# TOP.net
KiCad netlist of a schematic drawn in Altium Designer
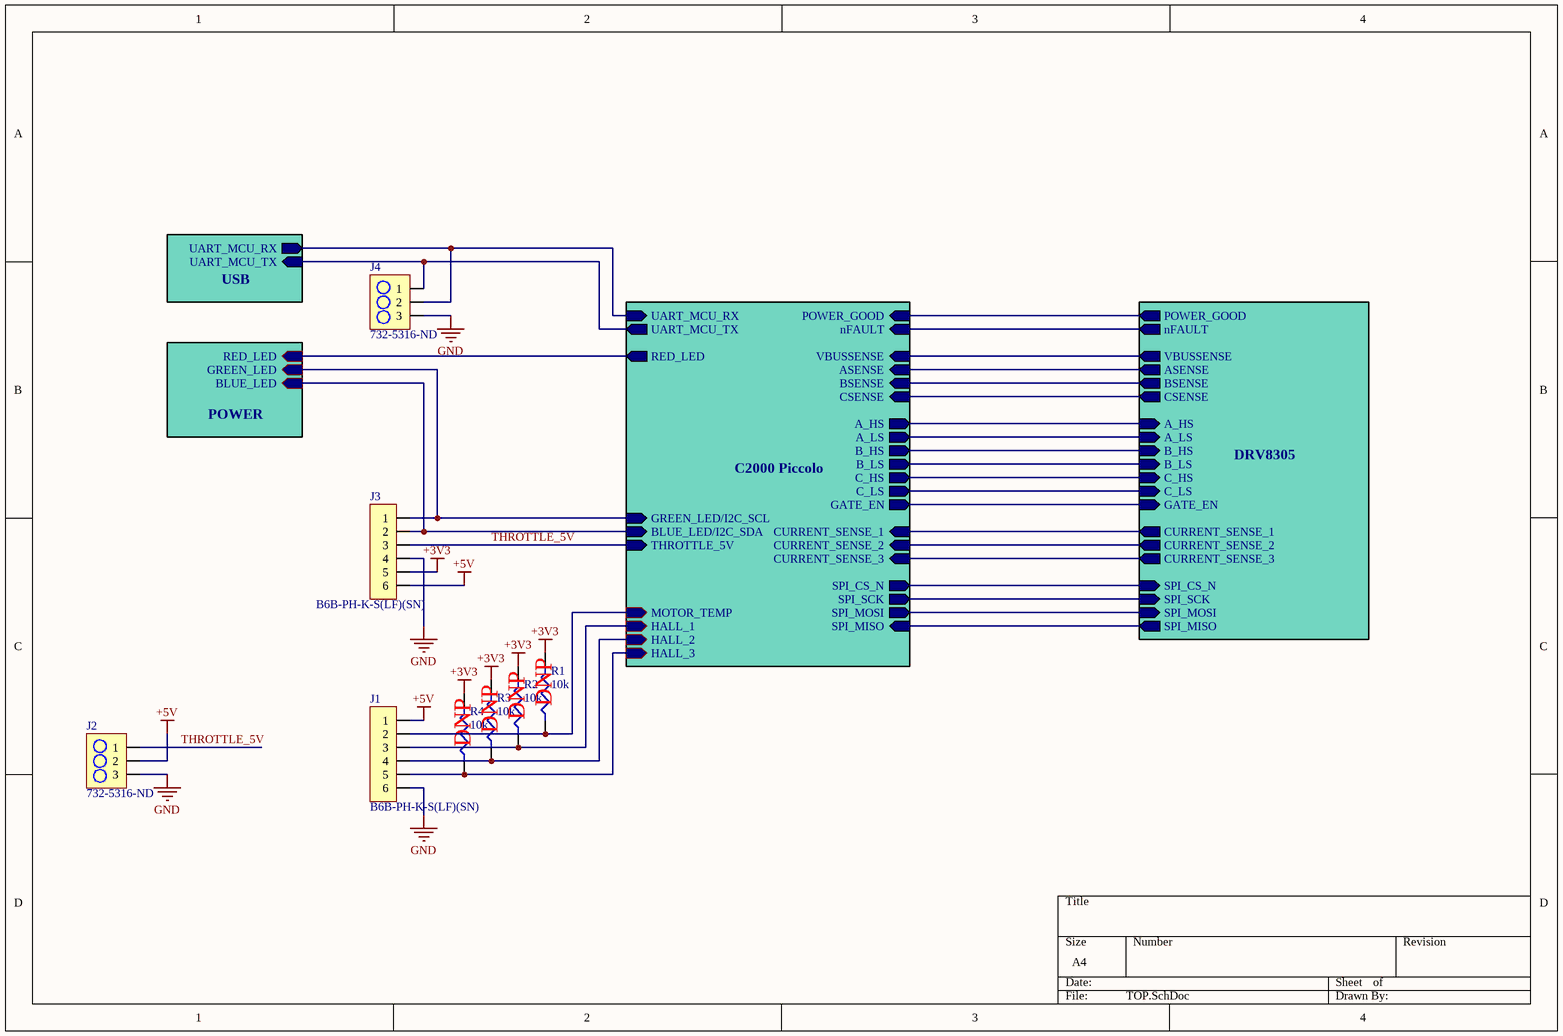
[diagram p0: TOP.SchDoc]

(export (version "E")
  (design (tool "Eeschema 10.0.6"))
  (components
    (comp (ref "J1")
      (value "B6B-PH-K-S(LF)(SN)")
      (footprint "JST-PH-6")
      (description "CONN JST PH 6 Positions Header, Shrouded Connector 0.079\" (2.00mm) Through Hole Tin")
      (fields (field (name "MANUFACTURER") "JST"))
      (libsource (lib "ESC_SYMBOLS") (part "B6B-PH-K-S(LF)(SN)"))
    )
    (comp (ref "J2")
      (value "732-5316-ND")
      (footprint "3PIN_HEADER")
      (fields
        (field (name "MANUFACTURER") "Wurth Electronics")
        (field (name "MANUFACTURER PART NUMBER") "61300311121")
      )
      (libsource (lib "ESC_SYMBOLS") (part "61300311121"))
    )
    (comp (ref "J3")
      (value "B6B-PH-K-S(LF)(SN)")
      (footprint "JST-PH-6")
      (description "CONN JST PH 6 Positions Header, Shrouded Connector 0.079\" (2.00mm) Through Hole Tin")
      (fields (field (name "MANUFACTURER") "JST"))
      (libsource (lib "ESC_SYMBOLS") (part "B6B-PH-K-S(LF)(SN)"))
    )
    (comp (ref "J4")
      (value "732-5316-ND")
      (footprint "3PIN_HEADER")
      (fields
        (field (name "MANUFACTURER") "Wurth Electronics")
        (field (name "MANUFACTURER PART NUMBER") "61300311121")
      )
      (libsource (lib "ESC_SYMBOLS") (part "61300311121"))
    )
    (comp (ref "R1")
      (value "10k")
      (footprint "R0402")
      (description "RES SMD 10K OHM 5% 1/16W 0402")
      (fields
        (field (name "MANUFACTURER") "Yageo")
        (field (name "MANUFACTURER PART NUMBER") "RC0402JR-0710KL")
      )
      (libsource (lib "ESC_SYMBOLS") (part "RC0402JR-0710KL"))
    )
    (comp (ref "R2")
      (value "10k")
      (footprint "R0402")
      (description "RES SMD 10K OHM 5% 1/16W 0402")
      (fields
        (field (name "MANUFACTURER") "Yageo")
        (field (name "MANUFACTURER PART NUMBER") "RC0402JR-0710KL")
      )
      (libsource (lib "ESC_SYMBOLS") (part "RC0402JR-0710KL"))
    )
    (comp (ref "R3")
      (value "10k")
      (footprint "R0402")
      (description "RES SMD 10K OHM 5% 1/16W 0402")
      (fields
        (field (name "MANUFACTURER") "Yageo")
        (field (name "MANUFACTURER PART NUMBER") "RC0402JR-0710KL")
      )
      (libsource (lib "ESC_SYMBOLS") (part "RC0402JR-0710KL"))
    )
    (comp (ref "R4")
      (value "10k")
      (footprint "R0402")
      (description "RES SMD 10K OHM 5% 1/16W 0402")
      (fields
        (field (name "MANUFACTURER") "Yageo")
        (field (name "MANUFACTURER PART NUMBER") "RC0402JR-0710KL")
      )
      (libsource (lib "ESC_SYMBOLS") (part "RC0402JR-0710KL"))
    )
  )
  (nets
    (net (code "1") (name "+3V3") (class "Default")
      (node (ref "J3") (pin "5") (pinfunction "5_5") (pintype "passive"))
      (node (ref "R1") (pin "2") (pinfunction "2_2") (pintype "passive"))
      (node (ref "R2") (pin "2") (pinfunction "2_2") (pintype "passive"))
      (node (ref "R3") (pin "2") (pinfunction "2_2") (pintype "passive"))
      (node (ref "R4") (pin "2") (pinfunction "2_2") (pintype "passive"))
    )
    (net (code "2") (name "+5V") (class "Default")
      (node (ref "J1") (pin "1") (pinfunction "1_1") (pintype "passive"))
      (node (ref "J2") (pin "2") (pinfunction "2_2") (pintype "passive"))
      (node (ref "J3") (pin "6") (pinfunction "6_6") (pintype "passive"))
    )
    (net (code "6") (name "/BLUE_LED") (class "Default")
      (node (ref "J3") (pin "2") (pinfunction "2_2") (pintype "passive"))
    )
    (net (code "17") (name "/GREEN_LED") (class "Default")
      (node (ref "J3") (pin "1") (pinfunction "1_1") (pintype "passive"))
    )
    (net (code "18") (name "/HALL_1") (class "Default")
      (node (ref "J1") (pin "3") (pinfunction "3_3") (pintype "passive"))
      (node (ref "R2") (pin "1") (pinfunction "1_1") (pintype "passive"))
    )
    (net (code "19") (name "/HALL_2") (class "Default")
      (node (ref "J1") (pin "4") (pinfunction "4_4") (pintype "passive"))
      (node (ref "R3") (pin "1") (pinfunction "1_1") (pintype "passive"))
    )
    (net (code "20") (name "/HALL_3") (class "Default")
      (node (ref "J1") (pin "5") (pinfunction "5_5") (pintype "passive"))
      (node (ref "R4") (pin "1") (pinfunction "1_1") (pintype "passive"))
    )
    (net (code "21") (name "/MOTOR_TEMP") (class "Default")
      (node (ref "J1") (pin "2") (pinfunction "2_2") (pintype "passive"))
      (node (ref "R1") (pin "1") (pinfunction "1_1") (pintype "passive"))
    )
    (net (code "28") (name "/THROTTLE_5V") (class "Default")
      (node (ref "J2") (pin "1") (pinfunction "1_1") (pintype "passive"))
      (node (ref "J3") (pin "3") (pinfunction "3_3") (pintype "passive"))
    )
    (net (code "29") (name "/UART_MCU_RX") (class "Default")
      (node (ref "J4") (pin "2") (pinfunction "2_2") (pintype "passive"))
    )
    (net (code "30") (name "/UART_MCU_TX") (class "Default")
      (node (ref "J4") (pin "1") (pinfunction "1_1") (pintype "passive"))
    )
    (net (code "33") (name "GND") (class "Default")
      (node (ref "J1") (pin "6") (pinfunction "6_6") (pintype "passive"))
      (node (ref "J2") (pin "3") (pinfunction "3_3") (pintype "passive"))
      (node (ref "J3") (pin "4") (pinfunction "4_4") (pintype "passive"))
      (node (ref "J4") (pin "3") (pinfunction "3_3") (pintype "passive"))
    )
  )
)
